# main.net
KiCad netlist of a schematic drawn in Altium Designer
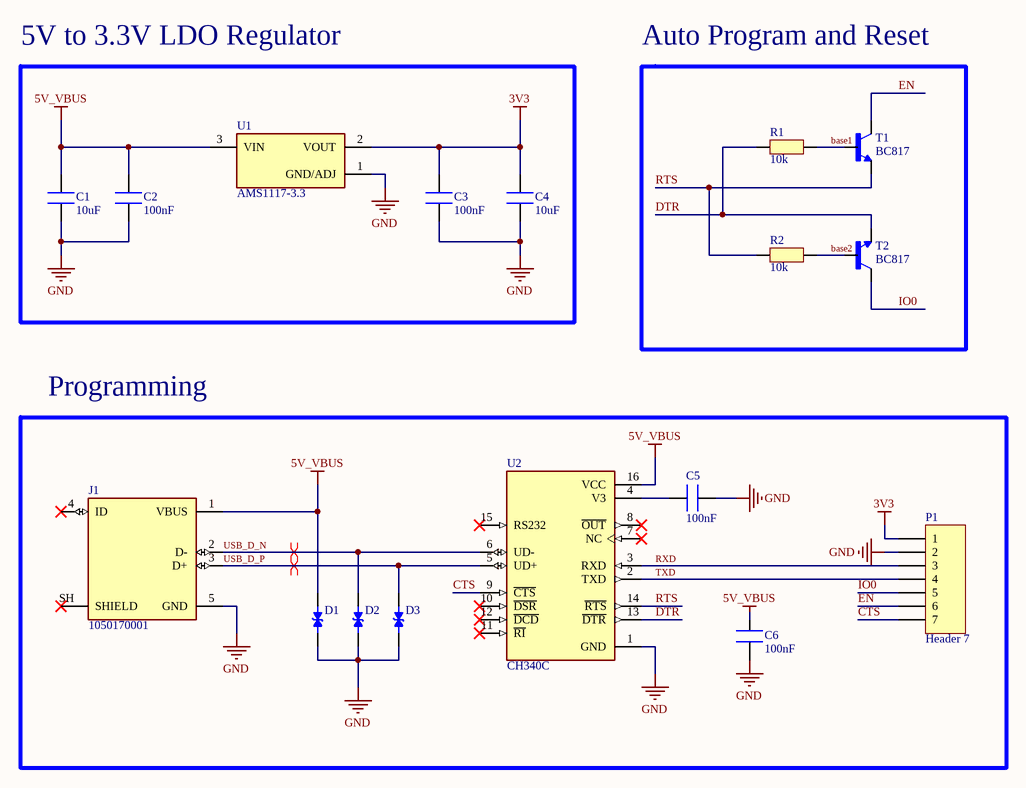
[diagram p0: main.SchDoc]

(export (version "E")
  (design (tool "Eeschema 10.0.6"))
  (components
    (comp (ref "C1")
      (value "10uF")
      (footprint "CAP_0603")
      (description "Capacitor SMD 0603 Generic")
      (libsource (lib "GenericCompLib") (part "Cap_0603"))
    )
    (comp (ref "C2")
      (value "100nF")
      (footprint "CAP_0603")
      (description "Capacitor SMD 0603 Generic")
      (libsource (lib "GenericCompLib") (part "Cap_0603"))
    )
    (comp (ref "C3")
      (value "100nF")
      (footprint "CAP_0603")
      (description "Capacitor SMD 0603 Generic")
      (libsource (lib "GenericCompLib") (part "Cap_0603"))
    )
    (comp (ref "C4")
      (value "10uF")
      (footprint "CAP_0603")
      (description "Capacitor SMD 0603 Generic")
      (libsource (lib "GenericCompLib") (part "Cap_0603"))
    )
    (comp (ref "C5")
      (value "100nF")
      (footprint "CAP_0603")
      (description "Capacitor SMD 0603 Generic")
      (libsource (lib "GenericCompLib") (part "Cap_0603"))
    )
    (comp (ref "C6")
      (value "100nF")
      (footprint "CAP_0603")
      (description "Capacitor SMD 0603 Generic")
      (libsource (lib "GenericCompLib") (part "Cap_0603"))
    )
    (comp (ref "D1")
      (value "LESD5D5.0CT1G")
      (footprint "TVS_LESD5D5.0CT1G")
      (description "SOD-523 ESD Protection Devices ROHS / VRWM = 5V / VC = 11.6V / C = 15pF General Purpose speed")
      (libsource (lib "GenericCompLib") (part "TVSDiode"))
    )
    (comp (ref "D2")
      (value "LESD5D5.0CT1G")
      (footprint "TVS_LESD5D5.0CT1G")
      (description "SOD-523 ESD Protection Devices ROHS / VRWM = 5V / VC = 11.6V / C = 15pF General Purpose speed")
      (libsource (lib "GenericCompLib") (part "TVSDiode"))
    )
    (comp (ref "D3")
      (value "LESD5D5.0CT1G")
      (footprint "TVS_LESD5D5.0CT1G")
      (description "SOD-523 ESD Protection Devices ROHS / VRWM = 5V / VC = 11.6V / C = 15pF General Purpose speed")
      (libsource (lib "GenericCompLib") (part "TVSDiode"))
    )
    (comp (ref "J1")
      (value "1050170001")
      (footprint "MOLEX-1050170001")
      (description "USB - micro B USB 2.0 Receptacle Connector 5 Position Surface Mount, Right Angle; Through Hole")
      (libsource (lib "ConnLib") (part "Molex_1050170001"))
    )
    (comp (ref "P1")
      (value "Header 7")
      (footprint "HDR1X7")
      (description "Header, 7-Pin")
      (fields (field (name "PUBLISHER") "Altium Limited"))
      (libsource (lib "Miscellaneous Connectors") (part "Header 7"))
    )
    (comp (ref "R1")
      (value "10k")
      (footprint "RES_0603")
      (description "Resistor SMD 0603 Generic")
      (libsource (lib "GenericCompLib") (part "Res_0603"))
    )
    (comp (ref "R2")
      (value "10k")
      (footprint "RES_0603")
      (description "Resistor SMD 0603 Generic")
      (libsource (lib "GenericCompLib") (part "Res_0603"))
    )
    (comp (ref "T1")
      (value "BC817")
      (footprint "BJT_SOT-23-3_NPN")
      (description "BJT NPN Transistor SOT23-3 pkg")
      (libsource (lib "") (part "BJT_SOT23-3_1"))
    )
    (comp (ref "T2")
      (value "BC817")
      (footprint "BJT_SOT-23-3_NPN")
      (description "BJT NPN Transistor SOT23-3 pkg")
      (libsource (lib "GenericCompLib") (part "BJT_SOT23-3"))
    )
    (comp (ref "U1")
      (value "AMS1117-3.3")
      (footprint "SOT229P700X180-4N")
      (description "Sot223/Pkg 1-Amp 3.3-Volt Low Drop Out Voltage Regulatator")
      (libsource (lib "PowerSupplyICLib") (part "AMS1117-3.3"))
    )
    (comp (ref "U2")
      (value "CH340C")
      (footprint "CH340x-SOP16")
      (description "2Mbps Transceiver USB 2.0 SOP-16 USB ICs ROHS")
      (libsource (lib "ICLib") (part "CH340C"))
    )
  )
  (nets
    (net (code "1") (name "/CTS") (class "Default")
      (node (ref "P1") (pin "7") (pinfunction "7_7") (pintype "passive"))
      (node (ref "U2") (pin "9") (pinfunction "~{CTS}_9") (pintype "input"))
    )
    (net (code "2") (name "/DTR") (class "Default")
      (node (ref "R1") (pin "1") (pinfunction "1_1") (pintype "passive"))
      (node (ref "T2") (pin "2") (pinfunction "E_2") (pintype "passive"))
      (node (ref "U2") (pin "13") (pinfunction "~{DTR}_13") (pintype "output"))
    )
    (net (code "3") (name "/EN") (class "Default")
      (node (ref "P1") (pin "6") (pinfunction "6_6") (pintype "passive"))
      (node (ref "T1") (pin "3") (pinfunction "C_3") (pintype "passive"))
    )
    (net (code "4") (name "/IO0") (class "Default")
      (node (ref "P1") (pin "5") (pinfunction "5_5") (pintype "passive"))
      (node (ref "T2") (pin "3") (pinfunction "C_3") (pintype "passive"))
    )
    (net (code "5") (name "/RTS") (class "Default")
      (node (ref "R2") (pin "1") (pinfunction "1_1") (pintype "passive"))
      (node (ref "T1") (pin "2") (pinfunction "E_2") (pintype "passive"))
      (node (ref "U2") (pin "14") (pinfunction "~{RTS}_14") (pintype "output"))
    )
    (net (code "6") (name "/RXD") (class "Default")
      (node (ref "P1") (pin "3") (pinfunction "3_3") (pintype "passive"))
      (node (ref "U2") (pin "3") (pinfunction "RXD_3") (pintype "input"))
    )
    (net (code "7") (name "/TXD") (class "Default")
      (node (ref "P1") (pin "4") (pinfunction "4_4") (pintype "passive"))
      (node (ref "U2") (pin "2") (pinfunction "TXD_2") (pintype "output"))
    )
    (net (code "8") (name "/USB_D_N") (class "Default")
      (node (ref "D2") (pin "2") (pinfunction "2_2") (pintype "passive"))
      (node (ref "J1") (pin "2") (pinfunction "D-_2") (pintype "bidirectional"))
      (node (ref "U2") (pin "6") (pinfunction "UD-_6") (pintype "bidirectional"))
    )
    (net (code "9") (name "/USB_D_P") (class "Default")
      (node (ref "D3") (pin "2") (pinfunction "2_2") (pintype "passive"))
      (node (ref "J1") (pin "3") (pinfunction "D+_3") (pintype "bidirectional"))
      (node (ref "U2") (pin "5") (pinfunction "UD+_5") (pintype "bidirectional"))
    )
    (net (code "10") (name "/base1") (class "Default")
      (node (ref "R1") (pin "2") (pinfunction "2_2") (pintype "passive"))
      (node (ref "T1") (pin "1") (pinfunction "B_1") (pintype "passive"))
    )
    (net (code "11") (name "/base2") (class "Default")
      (node (ref "R2") (pin "2") (pinfunction "2_2") (pintype "passive"))
      (node (ref "T2") (pin "1") (pinfunction "B_1") (pintype "passive"))
    )
    (net (code "13") (name "3V3") (class "Default")
      (node (ref "C3") (pin "2") (pinfunction "2_2") (pintype "passive"))
      (node (ref "C4") (pin "2") (pinfunction "2_2") (pintype "passive"))
      (node (ref "P1") (pin "1") (pinfunction "1_1") (pintype "passive"))
      (node (ref "U1") (pin "2") (pinfunction "VOUT_2") (pintype "power_in"))
    )
    (net (code "14") (name "5V_VBUS") (class "Default")
      (node (ref "C1") (pin "2") (pinfunction "2_2") (pintype "passive"))
      (node (ref "C2") (pin "2") (pinfunction "2_2") (pintype "passive"))
      (node (ref "C6") (pin "1") (pinfunction "1_1") (pintype "passive"))
      (node (ref "D1") (pin "2") (pinfunction "2_2") (pintype "passive"))
      (node (ref "J1") (pin "1") (pinfunction "VBUS_1") (pintype "power_in"))
      (node (ref "U1") (pin "3") (pinfunction "VIN_3") (pintype "power_in"))
      (node (ref "U2") (pin "16") (pinfunction "VCC_16") (pintype "power_in"))
    )
    (net (code "15") (name "GND") (class "Default")
      (node (ref "C1") (pin "1") (pinfunction "1_1") (pintype "passive"))
      (node (ref "C2") (pin "1") (pinfunction "1_1") (pintype "passive"))
      (node (ref "C3") (pin "1") (pinfunction "1_1") (pintype "passive"))
      (node (ref "C4") (pin "1") (pinfunction "1_1") (pintype "passive"))
      (node (ref "C5") (pin "1") (pinfunction "1_1") (pintype "passive"))
      (node (ref "C6") (pin "2") (pinfunction "2_2") (pintype "passive"))
      (node (ref "D1") (pin "1") (pinfunction "1_1") (pintype "passive"))
      (node (ref "D2") (pin "1") (pinfunction "1_1") (pintype "passive"))
      (node (ref "D3") (pin "1") (pinfunction "1_1") (pintype "passive"))
      (node (ref "J1") (pin "5") (pinfunction "GND_5") (pintype "power_in"))
      (node (ref "P1") (pin "2") (pinfunction "2_2") (pintype "passive"))
      (node (ref "U1") (pin "1") (pinfunction "GND/ADJ_1") (pintype "power_in"))
      (node (ref "U2") (pin "1") (pinfunction "GND_1") (pintype "power_in"))
    )
    (net (code "16") (name "Net-(U2-V3)") (class "Default")
      (node (ref "C5") (pin "2") (pinfunction "2_2") (pintype "passive"))
      (node (ref "U2") (pin "4") (pinfunction "V3_4") (pintype "power_in"))
    )
    (net (code "17") (name "unconnected-(J1-ID-Pad4)") (class "Default")
      (node (ref "J1") (pin "4") (pinfunction "ID_4") (pintype "bidirectional+no_connect"))
    )
    (net (code "18") (name "unconnected-(J1-SHIELD-PadSH)") (class "Default")
      (node (ref "J1") (pin "SH") (pinfunction "SHIELD_SH") (pintype "passive+no_connect"))
    )
    (net (code "19") (name "unconnected-(U2-NC-Pad7)") (class "Default")
      (node (ref "U2") (pin "7") (pinfunction "NC_7") (pintype "input+no_connect"))
    )
    (net (code "20") (name "unconnected-(U2-RS232-Pad15)") (class "Default")
      (node (ref "U2") (pin "15") (pinfunction "RS232_15") (pintype "input+no_connect"))
    )
    (net (code "21") (name "unconnected-(U2-~{DCD}-Pad12)") (class "Default")
      (node (ref "U2") (pin "12") (pinfunction "~{DCD}_12") (pintype "input+no_connect"))
    )
    (net (code "22") (name "unconnected-(U2-~{DSR}-Pad10)") (class "Default")
      (node (ref "U2") (pin "10") (pinfunction "~{DSR}_10") (pintype "input+no_connect"))
    )
    (net (code "23") (name "unconnected-(U2-~{OUT}-Pad8)") (class "Default")
      (node (ref "U2") (pin "8") (pinfunction "~{OUT}_8") (pintype "output+no_connect"))
    )
    (net (code "24") (name "unconnected-(U2-~{RI}-Pad11)") (class "Default")
      (node (ref "U2") (pin "11") (pinfunction "~{RI}_11") (pintype "input+no_connect"))
    )
  )
)
